# hhv-dcdarknet-proto.net
KiCad netlist of a schematic drawn in EAGLE
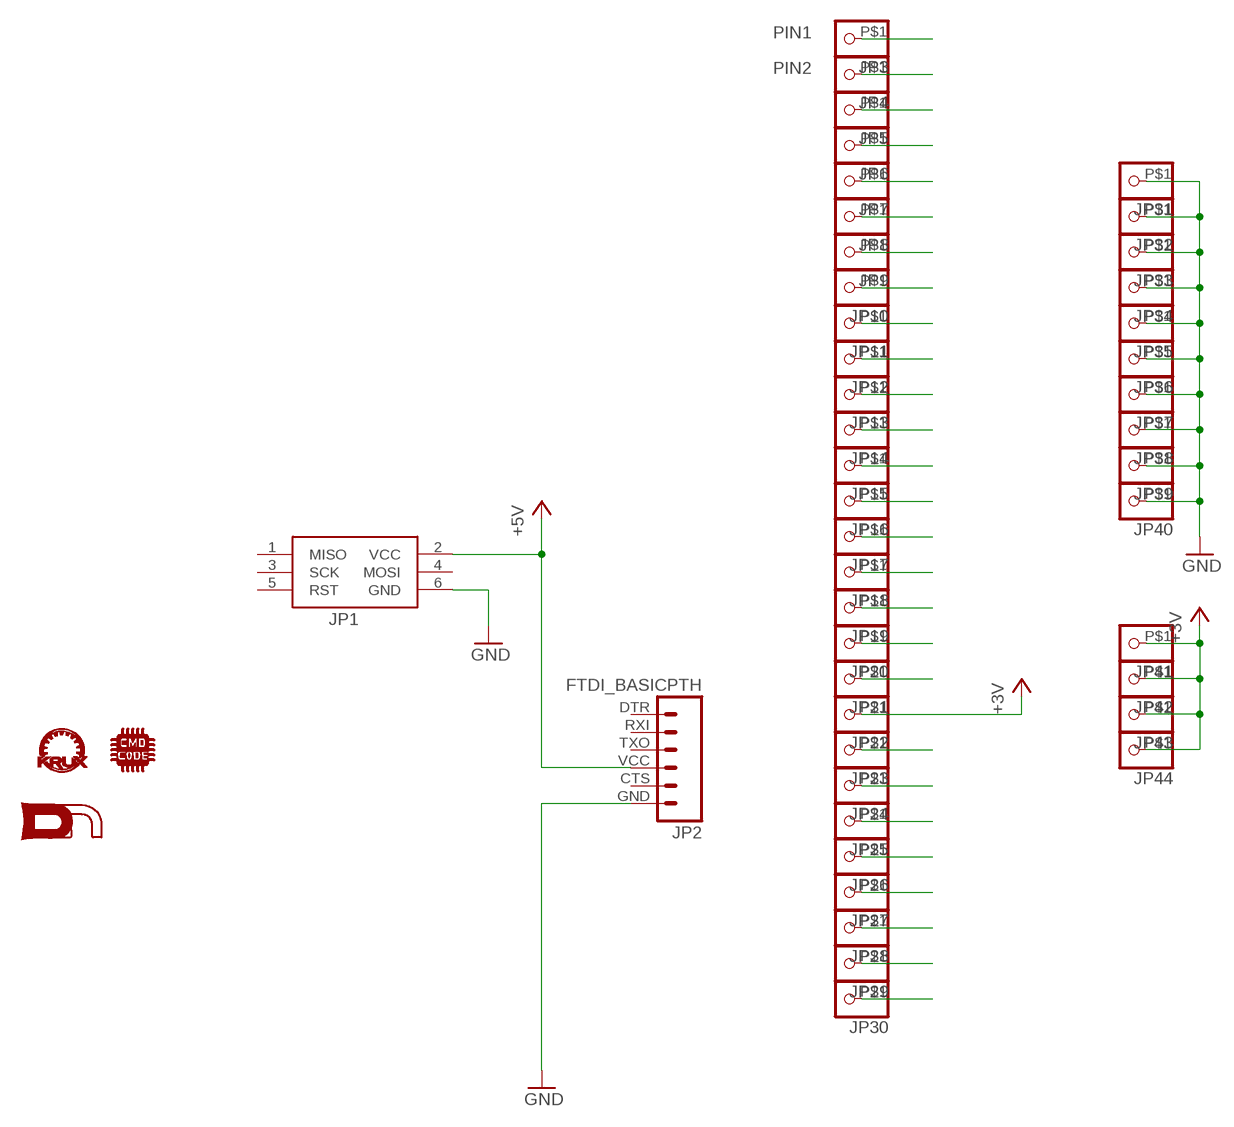
[diagram p0: schematic, sheet 1]

(export (version "E")
  (design (tool "Eeschema 10.0.6"))
  (components
    (comp (ref "JP1")
      (value "JP1")
      (footprint "eagle-import:AVRISP")
      (libsource (lib "eagle-import") (part "AVRISP-6"))
    )
    (comp (ref "JP2")
      (value "FTDI_BASICPTH")
      (footprint "eagle-import:FTDI_BASIC")
      (libsource (lib "eagle-import") (part "FTDI_BASICPTH"))
    )
    (comp (ref "JP3")
      (value "PINHD-1X11X1_SQUARE")
      (footprint "eagle-import:1X1-SMALL_CUT")
      (libsource (lib "eagle-import") (part "PINHD-1X11X1_SQUARE"))
    )
    (comp (ref "JP4")
      (value "PINHD-1X11X1_SQUARE")
      (footprint "eagle-import:1X1-SMALL_CUT")
      (libsource (lib "eagle-import") (part "PINHD-1X11X1_SQUARE"))
    )
    (comp (ref "JP5")
      (value "PINHD-1X11X1_SQUARE")
      (footprint "eagle-import:1X1-SMALL_CUT")
      (libsource (lib "eagle-import") (part "PINHD-1X11X1_SQUARE"))
    )
    (comp (ref "JP6")
      (value "PINHD-1X11X1_SQUARE")
      (footprint "eagle-import:1X1-SMALL_CUT")
      (libsource (lib "eagle-import") (part "PINHD-1X11X1_SQUARE"))
    )
    (comp (ref "JP7")
      (value "PINHD-1X11X1_SQUARE")
      (footprint "eagle-import:1X1-SMALL_CUT")
      (libsource (lib "eagle-import") (part "PINHD-1X11X1_SQUARE"))
    )
    (comp (ref "JP8")
      (value "PINHD-1X11X1_SQUARE")
      (footprint "eagle-import:1X1-SMALL_CUT")
      (libsource (lib "eagle-import") (part "PINHD-1X11X1_SQUARE"))
    )
    (comp (ref "JP9")
      (value "PINHD-1X11X1_SQUARE")
      (footprint "eagle-import:1X1-SMALL_CUT")
      (libsource (lib "eagle-import") (part "PINHD-1X11X1_SQUARE"))
    )
    (comp (ref "JP10")
      (value "PINHD-1X11X1_SQUARE")
      (footprint "eagle-import:1X1-SMALL_CUT")
      (libsource (lib "eagle-import") (part "PINHD-1X11X1_SQUARE"))
    )
    (comp (ref "JP11")
      (value "PINHD-1X11X1_SQUARE")
      (footprint "eagle-import:1X1-SMALL_CUT")
      (libsource (lib "eagle-import") (part "PINHD-1X11X1_SQUARE"))
    )
    (comp (ref "JP12")
      (value "PINHD-1X11X1_SQUARE")
      (footprint "eagle-import:1X1-SMALL_CUT")
      (libsource (lib "eagle-import") (part "PINHD-1X11X1_SQUARE"))
    )
    (comp (ref "JP13")
      (value "PINHD-1X11X1_SQUARE")
      (footprint "eagle-import:1X1-SMALL_CUT")
      (libsource (lib "eagle-import") (part "PINHD-1X11X1_SQUARE"))
    )
    (comp (ref "JP14")
      (value "PINHD-1X11X1_SQUARE")
      (footprint "eagle-import:1X1-SMALL_CUT")
      (libsource (lib "eagle-import") (part "PINHD-1X11X1_SQUARE"))
    )
    (comp (ref "JP15")
      (value "PINHD-1X11X1_SQUARE")
      (footprint "eagle-import:1X1-SMALL_CUT")
      (libsource (lib "eagle-import") (part "PINHD-1X11X1_SQUARE"))
    )
    (comp (ref "JP16")
      (value "PINHD-1X11X1_SQUARE")
      (footprint "eagle-import:1X1-SMALL_CUT")
      (libsource (lib "eagle-import") (part "PINHD-1X11X1_SQUARE"))
    )
    (comp (ref "JP17")
      (value "PINHD-1X11X1_SQUARE")
      (footprint "eagle-import:1X1-SMALL_CUT")
      (libsource (lib "eagle-import") (part "PINHD-1X11X1_SQUARE"))
    )
    (comp (ref "JP18")
      (value "PINHD-1X11X1_SQUARE")
      (footprint "eagle-import:1X1-SMALL_CUT")
      (libsource (lib "eagle-import") (part "PINHD-1X11X1_SQUARE"))
    )
    (comp (ref "JP19")
      (value "PINHD-1X11X1_SQUARE")
      (footprint "eagle-import:1X1-SMALL_CUT")
      (libsource (lib "eagle-import") (part "PINHD-1X11X1_SQUARE"))
    )
    (comp (ref "JP20")
      (value "PINHD-1X11X1_SQUARE")
      (footprint "eagle-import:1X1-SMALL_CUT")
      (libsource (lib "eagle-import") (part "PINHD-1X11X1_SQUARE"))
    )
    (comp (ref "JP21")
      (value "PINHD-1X11X1_SQUARE")
      (footprint "eagle-import:1X1-SMALL_CUT")
      (libsource (lib "eagle-import") (part "PINHD-1X11X1_SQUARE"))
    )
    (comp (ref "JP22")
      (value "PINHD-1X11X1_SQUARE")
      (footprint "eagle-import:1X1-SMALL_CUT")
      (libsource (lib "eagle-import") (part "PINHD-1X11X1_SQUARE"))
    )
    (comp (ref "JP23")
      (value "PINHD-1X11X1_SQUARE")
      (footprint "eagle-import:1X1-SMALL_CUT")
      (libsource (lib "eagle-import") (part "PINHD-1X11X1_SQUARE"))
    )
    (comp (ref "JP24")
      (value "PINHD-1X11X1_SQUARE")
      (footprint "eagle-import:1X1-SMALL_CUT")
      (libsource (lib "eagle-import") (part "PINHD-1X11X1_SQUARE"))
    )
    (comp (ref "JP25")
      (value "PINHD-1X11X1_SQUARE")
      (footprint "eagle-import:1X1-SMALL_CUT")
      (libsource (lib "eagle-import") (part "PINHD-1X11X1_SQUARE"))
    )
    (comp (ref "JP26")
      (value "PINHD-1X11X1_SQUARE")
      (footprint "eagle-import:1X1-SMALL_CUT")
      (libsource (lib "eagle-import") (part "PINHD-1X11X1_SQUARE"))
    )
    (comp (ref "JP27")
      (value "PINHD-1X11X1_SQUARE")
      (footprint "eagle-import:1X1-SMALL_CUT")
      (libsource (lib "eagle-import") (part "PINHD-1X11X1_SQUARE"))
    )
    (comp (ref "JP28")
      (value "PINHD-1X11X1_SQUARE")
      (footprint "eagle-import:1X1-SMALL_CUT")
      (libsource (lib "eagle-import") (part "PINHD-1X11X1_SQUARE"))
    )
    (comp (ref "JP29")
      (value "PINHD-1X11X1_SQUARE")
      (footprint "eagle-import:1X1-SMALL_CUT")
      (libsource (lib "eagle-import") (part "PINHD-1X11X1_SQUARE"))
    )
    (comp (ref "JP30")
      (value "PINHD-1X11X1_SQUARE")
      (footprint "eagle-import:1X1-SMALL_CUT")
      (libsource (lib "eagle-import") (part "PINHD-1X11X1_SQUARE"))
    )
    (comp (ref "JP31")
      (value "PINHD-1X11X1_SQUARE")
      (footprint "eagle-import:1X1-SMALL_CUT")
      (libsource (lib "eagle-import") (part "PINHD-1X11X1_SQUARE"))
    )
    (comp (ref "JP32")
      (value "PINHD-1X11X1_SQUARE")
      (footprint "eagle-import:1X1-SMALL_CUT")
      (libsource (lib "eagle-import") (part "PINHD-1X11X1_SQUARE"))
    )
    (comp (ref "JP33")
      (value "PINHD-1X11X1_SQUARE")
      (footprint "eagle-import:1X1-SMALL_CUT")
      (libsource (lib "eagle-import") (part "PINHD-1X11X1_SQUARE"))
    )
    (comp (ref "JP34")
      (value "PINHD-1X11X1_SQUARE")
      (footprint "eagle-import:1X1-SMALL_CUT")
      (libsource (lib "eagle-import") (part "PINHD-1X11X1_SQUARE"))
    )
    (comp (ref "JP35")
      (value "PINHD-1X11X1_SQUARE")
      (footprint "eagle-import:1X1-SMALL_CUT")
      (libsource (lib "eagle-import") (part "PINHD-1X11X1_SQUARE"))
    )
    (comp (ref "JP36")
      (value "PINHD-1X11X1_SQUARE")
      (footprint "eagle-import:1X1-SMALL_CUT")
      (libsource (lib "eagle-import") (part "PINHD-1X11X1_SQUARE"))
    )
    (comp (ref "JP37")
      (value "PINHD-1X11X1_SQUARE")
      (footprint "eagle-import:1X1-SMALL_CUT")
      (libsource (lib "eagle-import") (part "PINHD-1X11X1_SQUARE"))
    )
    (comp (ref "JP38")
      (value "PINHD-1X11X1_SQUARE")
      (footprint "eagle-import:1X1-SMALL_CUT")
      (libsource (lib "eagle-import") (part "PINHD-1X11X1_SQUARE"))
    )
    (comp (ref "JP39")
      (value "PINHD-1X11X1_SQUARE")
      (footprint "eagle-import:1X1-SMALL_CUT")
      (libsource (lib "eagle-import") (part "PINHD-1X11X1_SQUARE"))
    )
    (comp (ref "JP40")
      (value "PINHD-1X11X1_SQUARE")
      (footprint "eagle-import:1X1-SMALL_CUT")
      (libsource (lib "eagle-import") (part "PINHD-1X11X1_SQUARE"))
    )
    (comp (ref "JP41")
      (value "PINHD-1X11X1_SQUARE")
      (footprint "eagle-import:1X1-SMALL_CUT")
      (libsource (lib "eagle-import") (part "PINHD-1X11X1_SQUARE"))
    )
    (comp (ref "JP42")
      (value "PINHD-1X11X1_SQUARE")
      (footprint "eagle-import:1X1-SMALL_CUT")
      (libsource (lib "eagle-import") (part "PINHD-1X11X1_SQUARE"))
    )
    (comp (ref "JP43")
      (value "PINHD-1X11X1_SQUARE")
      (footprint "eagle-import:1X1-SMALL_CUT")
      (libsource (lib "eagle-import") (part "PINHD-1X11X1_SQUARE"))
    )
    (comp (ref "JP44")
      (value "PINHD-1X11X1_SQUARE")
      (footprint "eagle-import:1X1-SMALL_CUT")
      (libsource (lib "eagle-import") (part "PINHD-1X11X1_SQUARE"))
    )
    (comp (ref "U$1")
      (value "KRUX_LOGO")
      (footprint "eagle-import:KRUX_LOGO")
      (libsource (lib "eagle-import") (part "KRUX_LOGO"))
    )
    (comp (ref "U$2")
      (value "DN_LOGO")
      (footprint "eagle-import:DN_LOGO")
      (libsource (lib "eagle-import") (part "DN_LOGO"))
    )
    (comp (ref "U$3")
      (value "CMDC0DE_LOGO")
      (footprint "eagle-import:CMDC0DE")
      (libsource (lib "eagle-import") (part "CMDC0DE_LOGO"))
    )
  )
  (nets
    (net (code "1") (name "+3V") (class "Default")
      (node (ref "JP22") (pin "P$1") (pinfunction "1_P$1") (pintype "passive"))
      (node (ref "JP41") (pin "P$1") (pinfunction "1_P$1") (pintype "passive"))
      (node (ref "JP42") (pin "P$1") (pinfunction "1_P$1") (pintype "passive"))
      (node (ref "JP43") (pin "P$1") (pinfunction "1_P$1") (pintype "passive"))
      (node (ref "JP44") (pin "P$1") (pinfunction "1_P$1") (pintype "passive"))
      (node (ref "JP9") (pin "P$1") (pinfunction "1_P$1") (pintype "passive"))
    )
    (net (code "2") (name "+5V") (class "Default")
      (node (ref "JP1") (pin "2") (pinfunction "VCC_2") (pintype "power_in"))
      (node (ref "JP2") (pin "VCC") (pinfunction "4_VCC") (pintype "passive"))
    )
    (net (code "3") (name "/PIN1") (class "Default")
      (node (ref "JP3") (pin "P$1") (pinfunction "1_P$1") (pintype "passive"))
    )
    (net (code "4") (name "/PIN2") (class "Default")
      (node (ref "JP4") (pin "P$1") (pinfunction "1_P$1") (pintype "passive"))
    )
    (net (code "5") (name "GND") (class "Default")
      (node (ref "JP1") (pin "6") (pinfunction "GND_6") (pintype "power_in"))
      (node (ref "JP10") (pin "P$1") (pinfunction "1_P$1") (pintype "passive"))
      (node (ref "JP2") (pin "GND") (pinfunction "6_GND") (pintype "passive"))
      (node (ref "JP31") (pin "P$1") (pinfunction "1_P$1") (pintype "passive"))
      (node (ref "JP32") (pin "P$1") (pinfunction "1_P$1") (pintype "passive"))
      (node (ref "JP33") (pin "P$1") (pinfunction "1_P$1") (pintype "passive"))
      (node (ref "JP34") (pin "P$1") (pinfunction "1_P$1") (pintype "passive"))
      (node (ref "JP35") (pin "P$1") (pinfunction "1_P$1") (pintype "passive"))
      (node (ref "JP36") (pin "P$1") (pinfunction "1_P$1") (pintype "passive"))
      (node (ref "JP37") (pin "P$1") (pinfunction "1_P$1") (pintype "passive"))
      (node (ref "JP38") (pin "P$1") (pinfunction "1_P$1") (pintype "passive"))
      (node (ref "JP39") (pin "P$1") (pinfunction "1_P$1") (pintype "passive"))
      (node (ref "JP40") (pin "P$1") (pinfunction "1_P$1") (pintype "passive"))
    )
    (net (code "6") (name "unconnected-(JP1-MISO-Pad1)") (class "Default")
      (node (ref "JP1") (pin "1") (pinfunction "MISO_1") (pintype "input"))
    )
    (net (code "7") (name "unconnected-(JP1-MOSI-Pad4)") (class "Default")
      (node (ref "JP1") (pin "4") (pinfunction "MOSI_4") (pintype "output"))
    )
    (net (code "8") (name "unconnected-(JP1-RST-Pad5)") (class "Default")
      (node (ref "JP1") (pin "5") (pinfunction "RST_5") (pintype "output"))
    )
    (net (code "9") (name "unconnected-(JP1-SCK-Pad3)") (class "Default")
      (node (ref "JP1") (pin "3") (pinfunction "SCK_3") (pintype "output"))
    )
    (net (code "10") (name "unconnected-(JP2-1-PadDTR)") (class "Default")
      (node (ref "JP2") (pin "DTR") (pinfunction "1_DTR") (pintype "passive"))
    )
    (net (code "11") (name "unconnected-(JP2-2-PadRXI)") (class "Default")
      (node (ref "JP2") (pin "RXI") (pinfunction "2_RXI") (pintype "passive"))
    )
    (net (code "12") (name "unconnected-(JP2-3-PadTXO)") (class "Default")
      (node (ref "JP2") (pin "TXO") (pinfunction "3_TXO") (pintype "passive"))
    )
    (net (code "13") (name "unconnected-(JP2-5-PadCTS)") (class "Default")
      (node (ref "JP2") (pin "CTS") (pinfunction "5_CTS") (pintype "passive"))
    )
    (net (code "14") (name "unconnected-(JP5-1-PadP$1)") (class "Default")
      (node (ref "JP5") (pin "P$1") (pinfunction "1_P$1") (pintype "passive"))
    )
    (net (code "15") (name "unconnected-(JP6-1-PadP$1)") (class "Default")
      (node (ref "JP6") (pin "P$1") (pinfunction "1_P$1") (pintype "passive"))
    )
    (net (code "16") (name "unconnected-(JP7-1-PadP$1)") (class "Default")
      (node (ref "JP7") (pin "P$1") (pinfunction "1_P$1") (pintype "passive"))
    )
    (net (code "17") (name "unconnected-(JP8-1-PadP$1)") (class "Default")
      (node (ref "JP8") (pin "P$1") (pinfunction "1_P$1") (pintype "passive"))
    )
    (net (code "18") (name "unconnected-(JP11-1-PadP$1)") (class "Default")
      (node (ref "JP11") (pin "P$1") (pinfunction "1_P$1") (pintype "passive"))
    )
    (net (code "19") (name "unconnected-(JP12-1-PadP$1)") (class "Default")
      (node (ref "JP12") (pin "P$1") (pinfunction "1_P$1") (pintype "passive"))
    )
    (net (code "20") (name "unconnected-(JP13-1-PadP$1)") (class "Default")
      (node (ref "JP13") (pin "P$1") (pinfunction "1_P$1") (pintype "passive"))
    )
    (net (code "21") (name "unconnected-(JP14-1-PadP$1)") (class "Default")
      (node (ref "JP14") (pin "P$1") (pinfunction "1_P$1") (pintype "passive"))
    )
    (net (code "22") (name "unconnected-(JP15-1-PadP$1)") (class "Default")
      (node (ref "JP15") (pin "P$1") (pinfunction "1_P$1") (pintype "passive"))
    )
    (net (code "23") (name "unconnected-(JP16-1-PadP$1)") (class "Default")
      (node (ref "JP16") (pin "P$1") (pinfunction "1_P$1") (pintype "passive"))
    )
    (net (code "24") (name "unconnected-(JP17-1-PadP$1)") (class "Default")
      (node (ref "JP17") (pin "P$1") (pinfunction "1_P$1") (pintype "passive"))
    )
    (net (code "25") (name "unconnected-(JP18-1-PadP$1)") (class "Default")
      (node (ref "JP18") (pin "P$1") (pinfunction "1_P$1") (pintype "passive"))
    )
    (net (code "26") (name "unconnected-(JP19-1-PadP$1)") (class "Default")
      (node (ref "JP19") (pin "P$1") (pinfunction "1_P$1") (pintype "passive"))
    )
    (net (code "27") (name "unconnected-(JP20-1-PadP$1)") (class "Default")
      (node (ref "JP20") (pin "P$1") (pinfunction "1_P$1") (pintype "passive"))
    )
    (net (code "28") (name "unconnected-(JP21-1-PadP$1)") (class "Default")
      (node (ref "JP21") (pin "P$1") (pinfunction "1_P$1") (pintype "passive"))
    )
    (net (code "29") (name "unconnected-(JP23-1-PadP$1)") (class "Default")
      (node (ref "JP23") (pin "P$1") (pinfunction "1_P$1") (pintype "passive"))
    )
    (net (code "30") (name "unconnected-(JP24-1-PadP$1)") (class "Default")
      (node (ref "JP24") (pin "P$1") (pinfunction "1_P$1") (pintype "passive"))
    )
    (net (code "31") (name "unconnected-(JP25-1-PadP$1)") (class "Default")
      (node (ref "JP25") (pin "P$1") (pinfunction "1_P$1") (pintype "passive"))
    )
    (net (code "32") (name "unconnected-(JP26-1-PadP$1)") (class "Default")
      (node (ref "JP26") (pin "P$1") (pinfunction "1_P$1") (pintype "passive"))
    )
    (net (code "33") (name "unconnected-(JP27-1-PadP$1)") (class "Default")
      (node (ref "JP27") (pin "P$1") (pinfunction "1_P$1") (pintype "passive"))
    )
    (net (code "34") (name "unconnected-(JP28-1-PadP$1)") (class "Default")
      (node (ref "JP28") (pin "P$1") (pinfunction "1_P$1") (pintype "passive"))
    )
    (net (code "35") (name "unconnected-(JP29-1-PadP$1)") (class "Default")
      (node (ref "JP29") (pin "P$1") (pinfunction "1_P$1") (pintype "passive"))
    )
    (net (code "36") (name "unconnected-(JP30-1-PadP$1)") (class "Default")
      (node (ref "JP30") (pin "P$1") (pinfunction "1_P$1") (pintype "passive"))
    )
  )
)
